# ControlBoard.net
KiCad netlist of a schematic drawn in Altium Designer
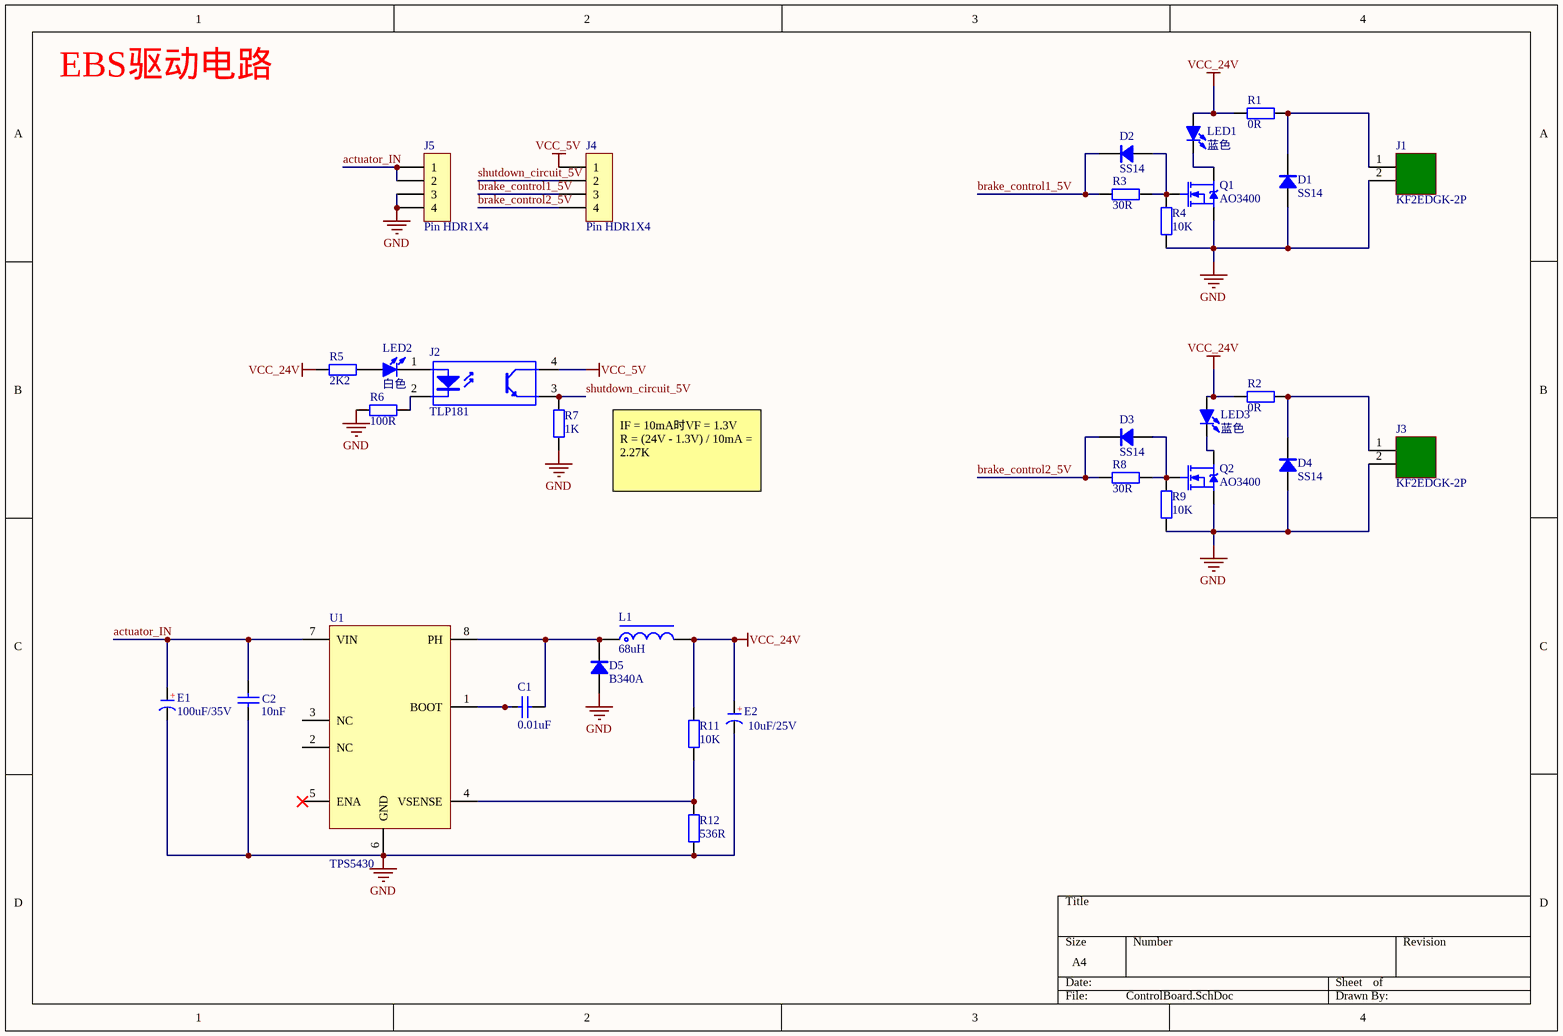
[diagram p0: ControlBoard.SchDoc]

(export (version "E")
  (design (tool "Eeschema 10.0.6"))
  (components
    (comp (ref "C1")
      (value "0.01uF")
      (footprint "C 0805_M")
      (description "无极性贴片电容")
      (libsource (lib "mainlib") (part "C"))
    )
    (comp (ref "C2")
      (value "10nF")
      (footprint "C 0805_M")
      (description "无极性贴片电容")
      (libsource (lib "mainlib") (part "C"))
    )
    (comp (ref "D1")
      (value "SS14")
      (footprint "SMA")
      (description "肖特基二极管")
      (fields (field (name "版权归属") "源创客"))
      (libsource (lib "mainlib") (part "SS14"))
    )
    (comp (ref "D2")
      (value "SS14")
      (footprint "SMA")
      (description "肖特基二极管")
      (fields (field (name "版权归属") "源创客"))
      (libsource (lib "mainlib") (part "SS14"))
    )
    (comp (ref "D3")
      (value "SS14")
      (footprint "SMA")
      (description "肖特基二极管")
      (fields (field (name "版权归属") "源创客"))
      (libsource (lib "mainlib") (part "SS14"))
    )
    (comp (ref "D4")
      (value "SS14")
      (footprint "SMA")
      (description "肖特基二极管")
      (fields (field (name "版权归属") "源创客"))
      (libsource (lib "mainlib") (part "SS14"))
    )
    (comp (ref "D5")
      (value "B340A")
      (footprint "SMA")
      (description "肖特基二极管\r\n反向耐压大于28.5V")
      (fields (field (name "版权归属") "源创客"))
      (libsource (lib "mainlib") (part "SS34"))
    )
    (comp (ref "E1")
      (value "100uF/35V")
      (footprint "CM D(6.3*7.7)")
      (description "贴片电解电容\r\nESR < 0.04R")
      (fields (field (name "版权归属") "源创客"))
      (libsource (lib "mainlib") (part "C-CM"))
    )
    (comp (ref "E2")
      (value "10uF/25V")
      (footprint "CM C(5*5.4)")
      (description "贴片电解电容\r\nESR < 0.088R\r\nV>24.0004V")
      (fields (field (name "版权归属") "源创客"))
      (libsource (lib "mainlib") (part "C-CM"))
    )
    (comp (ref "J1")
      (value "KF2EDGK-2P")
      (footprint "KF2EDGK5.08W-2P")
      (libsource (lib "mainlib") (part "KF2EDGK-2P"))
    )
    (comp (ref "J2")
      (value "TLP181")
      (footprint "SOP4")
      (description "光耦")
      (fields (field (name "版权归属") "源创客"))
      (libsource (lib "mainlib") (part "TLP181"))
    )
    (comp (ref "J3")
      (value "KF2EDGK-2P")
      (footprint "KF2EDGK5.08W-2P")
      (libsource (lib "mainlib") (part "KF2EDGK-2P"))
    )
    (comp (ref "J4")
      (value "Pin HDR1X4")
      (footprint "Pin HDR1X4/2.54mm-S")
      (libsource (lib "mainlib") (part "Pin HDR1X4"))
    )
    (comp (ref "J5")
      (value "Pin HDR1X4")
      (footprint "Pin HDR1X4/2.54mm-S")
      (libsource (lib "mainlib") (part "Pin HDR1X4"))
    )
    (comp (ref "L1")
      (value "68uH")
      (footprint "SMD,6.0*6.0")
      (description "贴片功率电感\r\nIrms>0.500003A\r\nIpk>0.563A")
      (fields (field (name "版权归属") "源创客"))
      (libsource (lib "mainlib") (part "L-CD"))
    )
    (comp (ref "LED1")
      (value "蓝色")
      (footprint "LED 0805B")
      (description "贴片LED")
      (fields (field (name "版权归属") "源创客"))
      (libsource (lib "mainlib") (part "LED-SMD"))
    )
    (comp (ref "LED2")
      (value "白色")
      (footprint "LED 0805W")
      (description "贴片LED")
      (fields (field (name "版权归属") "源创客"))
      (libsource (lib "mainlib") (part "LED-SMD"))
    )
    (comp (ref "LED3")
      (value "蓝色")
      (footprint "LED 0805B")
      (description "贴片LED")
      (fields (field (name "版权归属") "源创客"))
      (libsource (lib "mainlib") (part "LED-SMD"))
    )
    (comp (ref "Q1")
      (value "AO3400")
      (footprint "SOT23")
      (description "N沟道场效应管")
      (libsource (lib "mainlib") (part "N-MOS"))
    )
    (comp (ref "Q2")
      (value "AO3400")
      (footprint "SOT23")
      (description "N沟道场效应管")
      (libsource (lib "mainlib") (part "N-MOS"))
    )
    (comp (ref "R1")
      (value "0R")
      (footprint "0805R")
      (description "贴片电阻")
      (libsource (lib "mainlib") (part "RES"))
    )
    (comp (ref "R2")
      (value "0R")
      (footprint "0805R")
      (description "贴片电阻")
      (libsource (lib "mainlib") (part "RES"))
    )
    (comp (ref "R3")
      (value "30R")
      (footprint "0805R")
      (description "贴片电阻")
      (libsource (lib "mainlib") (part "RES"))
    )
    (comp (ref "R4")
      (value "10K")
      (footprint "0805R")
      (description "贴片电阻")
      (libsource (lib "") (part "RES_1"))
    )
    (comp (ref "R5")
      (value "2K2")
      (footprint "0805R")
      (description "贴片电阻")
      (libsource (lib "mainlib") (part "RES"))
    )
    (comp (ref "R6")
      (value "100R")
      (footprint "0805R")
      (description "贴片电阻")
      (libsource (lib "mainlib") (part "RES"))
    )
    (comp (ref "R7")
      (value "1K")
      (footprint "0805R")
      (description "贴片电阻")
      (libsource (lib "") (part "RES_1"))
    )
    (comp (ref "R8")
      (value "30R")
      (footprint "0805R")
      (description "贴片电阻")
      (libsource (lib "mainlib") (part "RES"))
    )
    (comp (ref "R9")
      (value "10K")
      (footprint "0805R")
      (description "贴片电阻")
      (libsource (lib "") (part "RES_1"))
    )
    (comp (ref "R11")
      (value "10K")
      (footprint "0805R")
      (description "贴片电阻")
      (libsource (lib "") (part "RES_2"))
    )
    (comp (ref "R12")
      (value "536R")
      (footprint "0805R")
      (description "贴片电阻")
      (libsource (lib "") (part "RES_2"))
    )
    (comp (ref "U1")
      (value "TPS5430")
      (footprint "SOP8-Pad")
      (description "DCDC降压芯片")
      (libsource (lib "mainlib") (part "TPS5430"))
    )
  )
  (nets
    (net (code "1") (name "/actuator_IN") (class "Default")
      (node (ref "C2") (pin "1") (pinfunction "1_1") (pintype "passive"))
      (node (ref "E1") (pin "1") (pinfunction "A_1") (pintype "passive"))
      (node (ref "J5") (pin "1") (pinfunction "1_1") (pintype "passive"))
      (node (ref "J5") (pin "2") (pinfunction "2_2") (pintype "passive"))
      (node (ref "U1") (pin "7") (pinfunction "VIN_7") (pintype "passive"))
    )
    (net (code "2") (name "/brake_control1_5V") (class "Default")
      (node (ref "D2") (pin "2") (pinfunction "K_2") (pintype "passive"))
      (node (ref "J4") (pin "3") (pinfunction "3_3") (pintype "passive"))
      (node (ref "R3") (pin "2") (pinfunction "2_2") (pintype "passive"))
    )
    (net (code "3") (name "/brake_control2_5V") (class "Default")
      (node (ref "D3") (pin "2") (pinfunction "K_2") (pintype "passive"))
      (node (ref "J4") (pin "4") (pinfunction "4_4") (pintype "passive"))
      (node (ref "R8") (pin "2") (pinfunction "2_2") (pintype "passive"))
    )
    (net (code "4") (name "/shutdown_circuit_5V") (class "Default")
      (node (ref "J2") (pin "3") (pinfunction "E_3") (pintype "passive"))
      (node (ref "J4") (pin "2") (pinfunction "2_2") (pintype "passive"))
      (node (ref "R7") (pin "1") (pinfunction "1_1") (pintype "passive"))
    )
    (net (code "5") (name "GND") (class "Default")
      (node (ref "C2") (pin "2") (pinfunction "2_2") (pintype "passive"))
      (node (ref "D1") (pin "1") (pinfunction "A_1") (pintype "passive"))
      (node (ref "D4") (pin "1") (pinfunction "A_1") (pintype "passive"))
      (node (ref "D5") (pin "1") (pinfunction "A_1") (pintype "passive"))
      (node (ref "E1") (pin "2") (pinfunction "K_2") (pintype "passive"))
      (node (ref "E2") (pin "2") (pinfunction "K_2") (pintype "passive"))
      (node (ref "J1") (pin "2") (pinfunction "2_2") (pintype "passive"))
      (node (ref "J3") (pin "2") (pinfunction "2_2") (pintype "passive"))
      (node (ref "J5") (pin "3") (pinfunction "3_3") (pintype "passive"))
      (node (ref "J5") (pin "4") (pinfunction "4_4") (pintype "passive"))
      (node (ref "Q1") (pin "S") (pinfunction "S_S") (pintype "passive"))
      (node (ref "Q2") (pin "S") (pinfunction "S_S") (pintype "passive"))
      (node (ref "R12") (pin "1") (pinfunction "1_1") (pintype "passive"))
      (node (ref "R4") (pin "2") (pinfunction "2_2") (pintype "passive"))
      (node (ref "R6") (pin "2") (pinfunction "2_2") (pintype "passive"))
      (node (ref "R7") (pin "2") (pinfunction "2_2") (pintype "passive"))
      (node (ref "R9") (pin "2") (pinfunction "2_2") (pintype "passive"))
      (node (ref "U1") (pin "6") (pinfunction "GND_6") (pintype "passive"))
    )
    (net (code "6") (name "Net-(D1-K)") (class "Default")
      (node (ref "D1") (pin "2") (pinfunction "K_2") (pintype "passive"))
      (node (ref "J1") (pin "1") (pinfunction "1_1") (pintype "passive"))
      (node (ref "R1") (pin "1") (pinfunction "1_1") (pintype "passive"))
    )
    (net (code "7") (name "Net-(D2-A)") (class "Default")
      (node (ref "D2") (pin "1") (pinfunction "A_1") (pintype "passive"))
      (node (ref "Q1") (pin "G") (pinfunction "G_G") (pintype "passive"))
      (node (ref "R3") (pin "1") (pinfunction "1_1") (pintype "passive"))
      (node (ref "R4") (pin "1") (pinfunction "1_1") (pintype "passive"))
    )
    (net (code "8") (name "Net-(D3-A)") (class "Default")
      (node (ref "D3") (pin "1") (pinfunction "A_1") (pintype "passive"))
      (node (ref "Q2") (pin "G") (pinfunction "G_G") (pintype "passive"))
      (node (ref "R8") (pin "1") (pinfunction "1_1") (pintype "passive"))
      (node (ref "R9") (pin "1") (pinfunction "1_1") (pintype "passive"))
    )
    (net (code "9") (name "Net-(D4-K)") (class "Default")
      (node (ref "D4") (pin "2") (pinfunction "K_2") (pintype "passive"))
      (node (ref "J3") (pin "1") (pinfunction "1_1") (pintype "passive"))
      (node (ref "R2") (pin "1") (pinfunction "1_1") (pintype "passive"))
    )
    (net (code "10") (name "Net-(D5-K)") (class "Default")
      (node (ref "C1") (pin "2") (pinfunction "2_2") (pintype "passive"))
      (node (ref "D5") (pin "2") (pinfunction "K_2") (pintype "passive"))
      (node (ref "L1") (pin "1") (pinfunction "1_1") (pintype "passive"))
      (node (ref "U1") (pin "8") (pinfunction "PH_8") (pintype "passive"))
    )
    (net (code "11") (name "Net-(J2-A)") (class "Default")
      (node (ref "J2") (pin "1") (pinfunction "A_1") (pintype "passive"))
      (node (ref "LED2") (pin "2") (pinfunction "K_2") (pintype "passive"))
    )
    (net (code "12") (name "Net-(J2-K)") (class "Default")
      (node (ref "J2") (pin "2") (pinfunction "K_2") (pintype "passive"))
      (node (ref "R6") (pin "1") (pinfunction "1_1") (pintype "passive"))
    )
    (net (code "13") (name "Net-(LED1-K)") (class "Default")
      (node (ref "LED1") (pin "2") (pinfunction "K_2") (pintype "passive"))
      (node (ref "Q1") (pin "D") (pinfunction "D_D") (pintype "passive"))
    )
    (net (code "14") (name "Net-(LED2-A)") (class "Default")
      (node (ref "LED2") (pin "1") (pinfunction "A_1") (pintype "passive"))
      (node (ref "R5") (pin "1") (pinfunction "1_1") (pintype "passive"))
    )
    (net (code "15") (name "Net-(LED3-K)") (class "Default")
      (node (ref "LED3") (pin "2") (pinfunction "K_2") (pintype "passive"))
      (node (ref "Q2") (pin "D") (pinfunction "D_D") (pintype "passive"))
    )
    (net (code "16") (name "Net-(U1-BOOT)") (class "Default")
      (node (ref "C1") (pin "1") (pinfunction "1_1") (pintype "passive"))
      (node (ref "U1") (pin "1") (pinfunction "BOOT_1") (pintype "passive"))
    )
    (net (code "17") (name "Net-(U1-VSENSE)") (class "Default")
      (node (ref "R11") (pin "1") (pinfunction "1_1") (pintype "passive"))
      (node (ref "R12") (pin "2") (pinfunction "2_2") (pintype "passive"))
      (node (ref "U1") (pin "4") (pinfunction "VSENSE_4") (pintype "passive"))
    )
    (net (code "18") (name "VCC_5V") (class "Default")
      (node (ref "J2") (pin "4") (pinfunction "C_4") (pintype "passive"))
      (node (ref "J4") (pin "1") (pinfunction "1_1") (pintype "passive"))
    )
    (net (code "19") (name "VCC_24V") (class "Default")
      (node (ref "E2") (pin "1") (pinfunction "A_1") (pintype "passive"))
      (node (ref "L1") (pin "2") (pinfunction "2_2") (pintype "passive"))
      (node (ref "LED1") (pin "1") (pinfunction "A_1") (pintype "passive"))
      (node (ref "LED3") (pin "1") (pinfunction "A_1") (pintype "passive"))
      (node (ref "R1") (pin "2") (pinfunction "2_2") (pintype "passive"))
      (node (ref "R11") (pin "2") (pinfunction "2_2") (pintype "passive"))
      (node (ref "R2") (pin "2") (pinfunction "2_2") (pintype "passive"))
      (node (ref "R5") (pin "2") (pinfunction "2_2") (pintype "passive"))
    )
    (net (code "20") (name "unconnected-(U1-ENA-Pad5)") (class "Default")
      (node (ref "U1") (pin "5") (pinfunction "ENA_5") (pintype "passive+no_connect"))
    )
    (net (code "21") (name "unconnected-(U1-NC-Pad2)") (class "Default")
      (node (ref "U1") (pin "2") (pinfunction "NC_2") (pintype "passive"))
    )
    (net (code "22") (name "unconnected-(U1-NC-Pad3)") (class "Default")
      (node (ref "U1") (pin "3") (pinfunction "NC_3") (pintype "passive"))
    )
  )
)
